# coringaM0.net
KiCad netlist of a schematic drawn in EAGLE
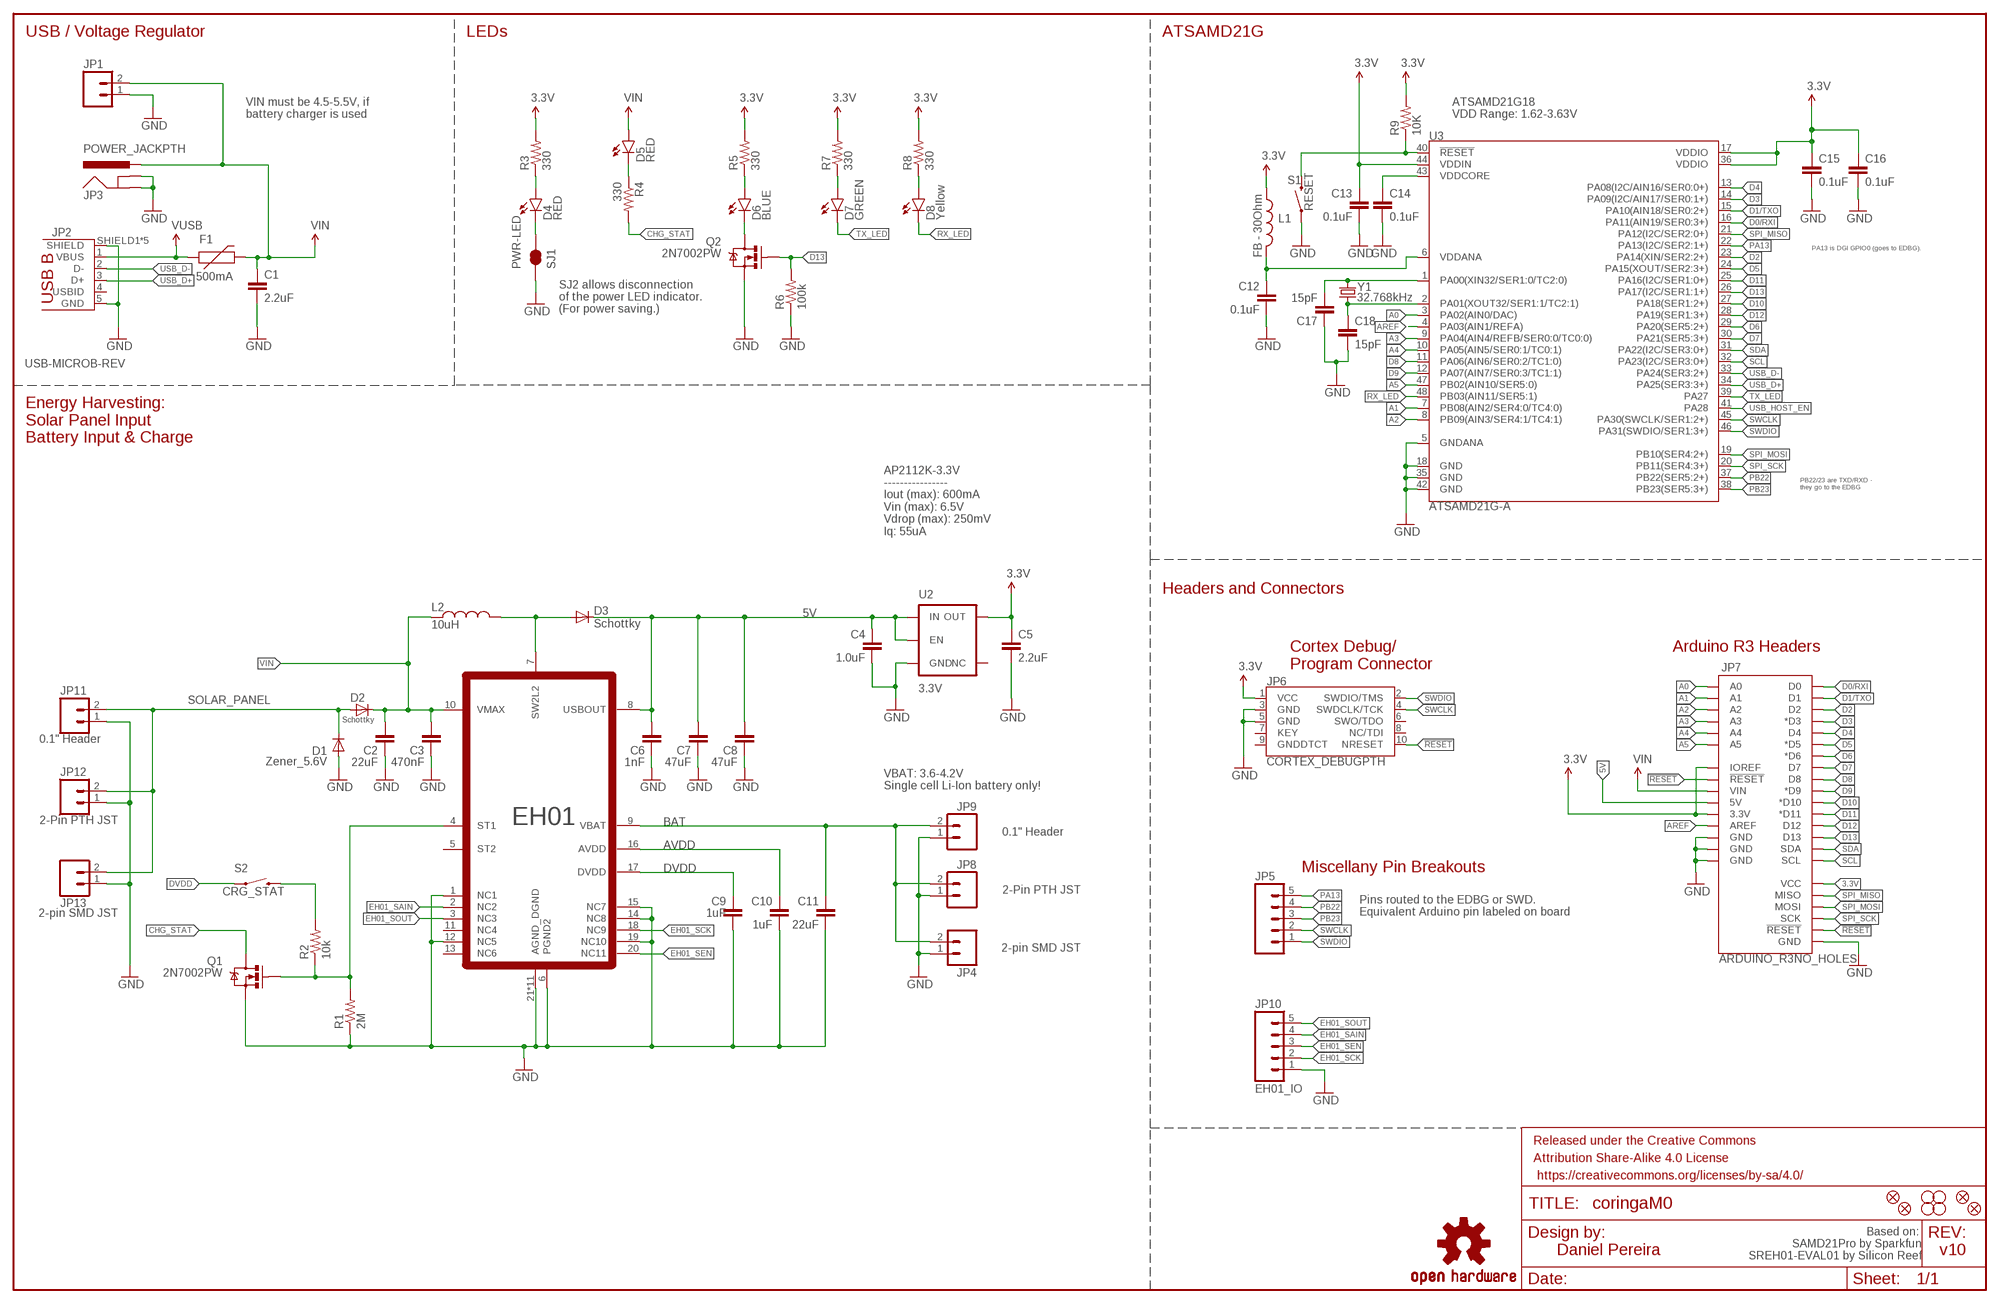
[diagram p0: schematic, sheet 1]

(export (version "E")
  (design (tool "Eeschema 10.0.6"))
  (components
    (comp (ref "C1")
      (value "2.2uF")
      (footprint "eagle-import:1206")
      (libsource (lib "eagle-import") (part "CAP1206"))
    )
    (comp (ref "C2")
      (value "22uF")
      (footprint "eagle-import:RCL_C0805")
      (libsource (lib "eagle-import") (part "CAPC0805"))
    )
    (comp (ref "C3")
      (value "470nF")
      (footprint "eagle-import:RCL_C1206")
      (libsource (lib "eagle-import") (part "CAPC1206"))
    )
    (comp (ref "C4")
      (value "1.0uF")
      (footprint "eagle-import:0805-CAP")
      (libsource (lib "eagle-import") (part "1.0UF-25V-+80/-20(0805){dblquote}"))
    )
    (comp (ref "C5")
      (value "2.2uF")
      (footprint "eagle-import:1206")
      (libsource (lib "eagle-import") (part "CAP1206"))
    )
    (comp (ref "C6")
      (value "1nF")
      (footprint "eagle-import:RCL_C1206K")
      (libsource (lib "eagle-import") (part "CAPC1206K"))
    )
    (comp (ref "C7")
      (value "47uF")
      (footprint "eagle-import:RCL_C1206K")
      (libsource (lib "eagle-import") (part "CAPC1206K"))
    )
    (comp (ref "C8")
      (value "47uF")
      (footprint "eagle-import:RCL_C1206K")
      (libsource (lib "eagle-import") (part "CAPC1206K"))
    )
    (comp (ref "C9")
      (value "1uF")
      (footprint "eagle-import:RCL_C0402")
      (libsource (lib "eagle-import") (part "CAPC0402"))
    )
    (comp (ref "C10")
      (value "1uF")
      (footprint "eagle-import:RCL_C0402")
      (libsource (lib "eagle-import") (part "CAPC0402"))
    )
    (comp (ref "C11")
      (value "22uF")
      (footprint "eagle-import:RCL_C0805")
      (libsource (lib "eagle-import") (part "CAPC0805"))
    )
    (comp (ref "C12")
      (value "0.1uF")
      (footprint "eagle-import:0603-CAP")
      (libsource (lib "eagle-import") (part "0.1UF-25V(+80/-20%)(0603)"))
    )
    (comp (ref "C13")
      (value "0.1uF")
      (footprint "eagle-import:0603-CAP")
      (libsource (lib "eagle-import") (part "0.1UF-25V(+80/-20%)(0603)"))
    )
    (comp (ref "C14")
      (value "0.1uF")
      (footprint "eagle-import:0603-CAP")
      (libsource (lib "eagle-import") (part "0.1UF-25V(+80/-20%)(0603)"))
    )
    (comp (ref "C15")
      (value "0.1uF")
      (footprint "eagle-import:0603-CAP")
      (libsource (lib "eagle-import") (part "0.1UF-25V(+80/-20%)(0603)"))
    )
    (comp (ref "C16")
      (value "0.1uF")
      (footprint "eagle-import:0603-CAP")
      (libsource (lib "eagle-import") (part "0.1UF-25V(+80/-20%)(0603)"))
    )
    (comp (ref "C17")
      (value "15pF")
      (footprint "eagle-import:0603-CAP")
      (libsource (lib "eagle-import") (part "15PF-50V-5%(0603)"))
    )
    (comp (ref "C18")
      (value "15pF")
      (footprint "eagle-import:0603-CAP")
      (libsource (lib "eagle-import") (part "15PF-50V-5%(0603)"))
    )
    (comp (ref "D1")
      (value "Zener_5.6V")
      (footprint "eagle-import:DO-214AC")
      (libsource (lib "eagle-import") (part "DIODE-DO-214AC"))
    )
    (comp (ref "D2")
      (value "Schottky")
      (footprint "eagle-import:DO-214AC")
      (libsource (lib "eagle-import") (part "DIODE-DO-214AC"))
    )
    (comp (ref "D3")
      (value "Schottky")
      (footprint "eagle-import:DO-214AC")
      (libsource (lib "eagle-import") (part "DIODE-DO-214AC"))
    )
    (comp (ref "D4")
      (value "RED")
      (footprint "eagle-import:LED-0603")
      (libsource (lib "eagle-import") (part "LED-RED0603"))
    )
    (comp (ref "D5")
      (value "RED")
      (footprint "eagle-import:LED-0603")
      (libsource (lib "eagle-import") (part "LED-RED0603"))
    )
    (comp (ref "D6")
      (value "BLUE")
      (footprint "eagle-import:LED-0603")
      (libsource (lib "eagle-import") (part "LED-BLUE0603"))
    )
    (comp (ref "D7")
      (value "GREEN")
      (footprint "eagle-import:LED-0603")
      (libsource (lib "eagle-import") (part "LED-GREEN0603"))
    )
    (comp (ref "D8")
      (value "Yellow")
      (footprint "eagle-import:LED-0603")
      (libsource (lib "eagle-import") (part "LED-YELLOW0603"))
    )
    (comp (ref "F1")
      (value "500mA")
      (footprint "eagle-import:PTC-1206")
      (libsource (lib "eagle-import") (part "PTCSMD"))
    )
    (comp (ref "FD1")
      (value "FIDUCIAL-VIA")
      (footprint "eagle-import:FIDUCIAL-VIA")
      (libsource (lib "eagle-import") (part "FIDUCIAL-VIA"))
    )
    (comp (ref "FD2")
      (value "FIDUCIAL-VIA")
      (footprint "eagle-import:FIDUCIAL-VIA")
      (libsource (lib "eagle-import") (part "FIDUCIAL-VIA"))
    )
    (comp (ref "FID1")
      (value "FIDUCIAL1X2")
      (footprint "eagle-import:FIDUCIAL-1X2")
      (libsource (lib "eagle-import") (part "FIDUCIAL1X2"))
    )
    (comp (ref "FID2")
      (value "FIDUCIAL1X2")
      (footprint "eagle-import:FIDUCIAL-1X2")
      (libsource (lib "eagle-import") (part "FIDUCIAL1X2"))
    )
    (comp (ref "FRAME1")
      (value "FRAME-LEDGER")
      (footprint "eagle-import:CREATIVE_COMMONS")
      (libsource (lib "eagle-import") (part "FRAME-LEDGER"))
    )
    (comp (ref "JP1")
      (value "M02PTH")
      (footprint "eagle-import:1X02")
      (libsource (lib "eagle-import") (part "M02PTH"))
    )
    (comp (ref "JP2")
      (value "USB-MICROB-REV")
      (footprint "eagle-import:USB-B-MICRO-REV-SMD")
      (fields (field (name "MPN") "ZX62R-B-5P"))
      (libsource (lib "eagle-import") (part "USB-MICROB-REV"))
    )
    (comp (ref "JP3")
      (value "POWER_JACKPTH")
      (footprint "eagle-import:POWER_JACK_PTH")
      (libsource (lib "eagle-import") (part "POWER_JACKPTH"))
    )
    (comp (ref "JP4")
      (value "M02-JST-2MM-SMT")
      (footprint "eagle-import:JST-2-SMD")
      (libsource (lib "eagle-import") (part "M02-JST-2MM-SMT"))
    )
    (comp (ref "JP5")
      (value "M05NO_SILK")
      (footprint "eagle-import:1X05_NO_SILK")
      (libsource (lib "eagle-import") (part "M05NO_SILK"))
    )
    (comp (ref "JP6")
      (value "CORTEX_DEBUGPTH")
      (footprint "eagle-import:2X5-PTH-1.27MM")
      (libsource (lib "eagle-import") (part "CORTEX_DEBUGPTH"))
    )
    (comp (ref "JP7")
      (value "ARDUINO_R3NO_HOLES")
      (footprint "eagle-import:ARDUINO_R3_NO_HOLES")
      (libsource (lib "eagle-import") (part "ARDUINO_R3NO_HOLES"))
    )
    (comp (ref "JP8")
      (value "M02-JST-2-PTH-NO_SILK")
      (footprint "eagle-import:JST-2-PTH-NS")
      (libsource (lib "eagle-import") (part "M02-JST-2-PTH-NO_SILK"))
    )
    (comp (ref "JP9")
      (value "M021X02_NO_SILK")
      (footprint "eagle-import:1X02_NO_SILK")
      (libsource (lib "eagle-import") (part "M021X02_NO_SILK"))
    )
    (comp (ref "JP10")
      (value "EH01_IO")
      (footprint "eagle-import:1X05_NO_SILK")
      (libsource (lib "eagle-import") (part "M05NO_SILK"))
    )
    (comp (ref "JP11")
      (value "M021X02_NO_SILK")
      (footprint "eagle-import:1X02_NO_SILK")
      (libsource (lib "eagle-import") (part "M021X02_NO_SILK"))
    )
    (comp (ref "JP12")
      (value "M02-JST-2-PTH-NO_SILK")
      (footprint "eagle-import:JST-2-PTH-NS")
      (libsource (lib "eagle-import") (part "M02-JST-2-PTH-NO_SILK"))
    )
    (comp (ref "JP13")
      (value "M02-JST-2MM-SMT")
      (footprint "eagle-import:JST-2-SMD")
      (libsource (lib "eagle-import") (part "M02-JST-2MM-SMT"))
    )
    (comp (ref "L1")
      (value "FB - 30Ohm")
      (footprint "eagle-import:0603")
      (libsource (lib "eagle-import") (part "INDUCTOR0603"))
    )
    (comp (ref "L2")
      (value "10uH")
      (footprint "eagle-import:SRN4065-100M")
      (libsource (lib "eagle-import") (part "INDUCTOR-SRN4065"))
    )
    (comp (ref "LOGO3")
      (value "OSHW-LOGOS")
      (footprint "eagle-import:OSHW-LOGO-S")
      (libsource (lib "eagle-import") (part "OSHW-LOGOS"))
    )
    (comp (ref "LOGO4")
      (value "OSHW-LOGOL")
      (footprint "eagle-import:OSHW-LOGO-L")
      (libsource (lib "eagle-import") (part "OSHW-LOGOL"))
    )
    (comp (ref "Q1")
      (value "2N7002PW")
      (footprint "eagle-import:SOT323")
      (libsource (lib "eagle-import") (part "MOSFET-NCHANNEL2N7002PW"))
    )
    (comp (ref "Q2")
      (value "2N7002PW")
      (footprint "eagle-import:SOT323")
      (libsource (lib "eagle-import") (part "MOSFET-NCHANNEL2N7002PW"))
    )
    (comp (ref "R1")
      (value "2M")
      (footprint "eagle-import:RESISTOR_R0402")
      (libsource (lib "eagle-import") (part "RESR0402"))
    )
    (comp (ref "R2")
      (value "10k")
      (footprint "eagle-import:RESISTOR_R0402")
      (libsource (lib "eagle-import") (part "RESR0402"))
    )
    (comp (ref "R3")
      (value "330")
      (footprint "eagle-import:0603-RES")
      (libsource (lib "eagle-import") (part "330OHM1/10W1%(0603)"))
    )
    (comp (ref "R4")
      (value "330")
      (footprint "eagle-import:0603-RES")
      (libsource (lib "eagle-import") (part "330OHM1/10W1%(0603)"))
    )
    (comp (ref "R5")
      (value "330")
      (footprint "eagle-import:0603-RES")
      (libsource (lib "eagle-import") (part "330OHM1/10W1%(0603)"))
    )
    (comp (ref "R6")
      (value "100k")
      (footprint "eagle-import:0603-RES")
      (libsource (lib "eagle-import") (part "100KOHM-1/10W-1%(0603)"))
    )
    (comp (ref "R7")
      (value "330")
      (footprint "eagle-import:0603-RES")
      (libsource (lib "eagle-import") (part "330OHM1/10W1%(0603)"))
    )
    (comp (ref "R8")
      (value "330")
      (footprint "eagle-import:0603-RES")
      (libsource (lib "eagle-import") (part "330OHM1/10W1%(0603)"))
    )
    (comp (ref "R9")
      (value "10K")
      (footprint "eagle-import:0603-RES")
      (libsource (lib "eagle-import") (part "10KOHM-1/10W-1%(0603)0603"))
    )
    (comp (ref "S1")
      (value "RESET")
      (footprint "eagle-import:TACTILE-SWITCH-SMD")
      (libsource (lib "eagle-import") (part "SWITCH-MOMENTARY-2SMD"))
    )
    (comp (ref "S2")
      (value "CRG_STAT")
      (footprint "eagle-import:TACTILE-SWITCH-SMD")
      (libsource (lib "eagle-import") (part "SWITCH-MOMENTARY-2SMD"))
    )
    (comp (ref "SJ1")
      (value "PWR-LED")
      (footprint "eagle-import:PAD-JUMPER-2-NC_BY_TRACE_NO_SILK")
      (libsource (lib "eagle-import") (part "JUMPER-PAD-2-NC_BY_TRACENO_SILK"))
    )
    (comp (ref "STANDOFF1")
      (value "STAND-OFF")
      (footprint "eagle-import:STAND-OFF")
      (libsource (lib "eagle-import") (part "STAND-OFF"))
    )
    (comp (ref "STANDOFF2")
      (value "STAND-OFF")
      (footprint "eagle-import:STAND-OFF")
      (libsource (lib "eagle-import") (part "STAND-OFF"))
    )
    (comp (ref "STANDOFF3")
      (value "STAND-OFF")
      (footprint "eagle-import:STAND-OFF")
      (libsource (lib "eagle-import") (part "STAND-OFF"))
    )
    (comp (ref "STANDOFF4")
      (value "STAND-OFF")
      (footprint "eagle-import:STAND-OFF")
      (libsource (lib "eagle-import") (part "STAND-OFF"))
    )
    (comp (ref "U1")
      (value "EH01")
      (footprint "eagle-import:QFN20")
      (libsource (lib "eagle-import") (part "EH01-P02"))
    )
    (comp (ref "U2")
      (value "3.3V")
      (footprint "eagle-import:SOT23-5")
      (libsource (lib "eagle-import") (part "V_REG_AP2112K-3.3V"))
    )
    (comp (ref "U3")
      (value "ATSAMD21G-A")
      (footprint "eagle-import:TQFP-48")
      (libsource (lib "eagle-import") (part "ATSAMD21G-A"))
    )
    (comp (ref "Y1")
      (value "32.768kHz")
      (footprint "eagle-import:CRYSTAL-SMD-3.2X1.5MM")
      (libsource (lib "eagle-import") (part "CRYSTAL3.2X1.5MM"))
    )
  )
  (nets
    (net (code "1") (name "/AVDD") (class "Default")
      (node (ref "C10") (pin "2") (pinfunction "2_2") (pintype "passive"))
      (node (ref "U1") (pin "16") (pinfunction "AVDD_16") (pintype "bidirectional"))
    )
    (net (code "2") (name "/BAT") (class "Default")
      (node (ref "C11") (pin "2") (pinfunction "2_2") (pintype "passive"))
      (node (ref "JP4") (pin "2") (pinfunction "1_2") (pintype "passive"))
      (node (ref "JP8") (pin "2") (pinfunction "2_2") (pintype "passive"))
      (node (ref "JP9") (pin "2") (pinfunction "2_2") (pintype "passive"))
      (node (ref "U1") (pin "9") (pinfunction "VBAT_9") (pintype "bidirectional"))
    )
    (net (code "3") (name "/SOLAR_PANEL") (class "Default")
      (node (ref "D1") (pin "C") (pinfunction "C_C") (pintype "passive"))
      (node (ref "D2") (pin "A") (pinfunction "A_A") (pintype "passive"))
      (node (ref "JP11") (pin "2") (pinfunction "2_2") (pintype "passive"))
      (node (ref "JP12") (pin "2") (pinfunction "2_2") (pintype "passive"))
      (node (ref "JP13") (pin "2") (pinfunction "1_2") (pintype "passive"))
    )
    (net (code "4") (name "/~{RESET}") (class "Default")
      (node (ref "JP6") (pin "10") (pinfunction "NRESET_10") (pintype "bidirectional"))
      (node (ref "JP7") (pin "RESET@1") (pinfunction "~{RESET}_RESET@1") (pintype "bidirectional"))
      (node (ref "JP7") (pin "RESET@2") (pinfunction "~{RESET}_RESET@2") (pintype "bidirectional"))
      (node (ref "R9") (pin "1") (pinfunction "1_1") (pintype "passive"))
      (node (ref "S1") (pin "3") (pinfunction "2_3") (pintype "passive"))
      (node (ref "U3") (pin "40") (pinfunction "~{RESET}_40") (pintype "bidirectional"))
    )
    (net (code "5") (name "3.3V") (class "Default")
      (node (ref "C13") (pin "1") (pinfunction "1_1") (pintype "passive"))
      (node (ref "C15") (pin "1") (pinfunction "1_1") (pintype "passive"))
      (node (ref "C16") (pin "1") (pinfunction "1_1") (pintype "passive"))
      (node (ref "C5") (pin "1") (pinfunction "1_1") (pintype "passive"))
      (node (ref "JP6") (pin "1") (pinfunction "VCC_1") (pintype "bidirectional"))
      (node (ref "JP7") (pin "3.3V") (pinfunction "3.3V_3.3V") (pintype "bidirectional"))
      (node (ref "JP7") (pin "IOREF") (pinfunction "IOREF_IOREF") (pintype "bidirectional"))
      (node (ref "JP7") (pin "VCC") (pinfunction "VCC_VCC") (pintype "bidirectional"))
      (node (ref "L1") (pin "1") (pinfunction "1_1") (pintype "passive"))
      (node (ref "R3") (pin "2") (pinfunction "2_2") (pintype "passive"))
      (node (ref "R5") (pin "2") (pinfunction "2_2") (pintype "passive"))
      (node (ref "R7") (pin "2") (pinfunction "2_2") (pintype "passive"))
      (node (ref "R8") (pin "2") (pinfunction "2_2") (pintype "passive"))
      (node (ref "R9") (pin "2") (pinfunction "2_2") (pintype "passive"))
      (node (ref "U2") (pin "5") (pinfunction "OUT_5") (pintype "passive"))
      (node (ref "U3") (pin "17") (pinfunction "VDDIO_17") (pintype "bidirectional"))
      (node (ref "U3") (pin "36") (pinfunction "VDDIO_36") (pintype "bidirectional"))
      (node (ref "U3") (pin "44") (pinfunction "VDDIN_44") (pintype "bidirectional"))
    )
    (net (code "6") (name "5V") (class "Default")
      (node (ref "C4") (pin "1") (pinfunction "1_1") (pintype "passive"))
      (node (ref "C6") (pin "2") (pinfunction "2_2") (pintype "passive"))
      (node (ref "C7") (pin "2") (pinfunction "2_2") (pintype "passive"))
      (node (ref "C8") (pin "2") (pinfunction "2_2") (pintype "passive"))
      (node (ref "D3") (pin "C") (pinfunction "C_C") (pintype "passive"))
      (node (ref "JP7") (pin "5V") (pinfunction "5V_5V") (pintype "bidirectional"))
      (node (ref "U1") (pin "8") (pinfunction "USBOUT_8") (pintype "bidirectional"))
      (node (ref "U2") (pin "1") (pinfunction "IN_1") (pintype "input"))
      (node (ref "U2") (pin "3") (pinfunction "EN_3") (pintype "input"))
    )
    (net (code "7") (name "A0") (class "Default")
      (node (ref "JP7") (pin "A0") (pinfunction "A0_A0") (pintype "bidirectional"))
      (node (ref "U3") (pin "3") (pinfunction "PA02(AIN0/DAC)_3") (pintype "bidirectional"))
    )
    (net (code "8") (name "A1") (class "Default")
      (node (ref "JP7") (pin "A1") (pinfunction "A1_A1") (pintype "bidirectional"))
      (node (ref "U3") (pin "7") (pinfunction "PB08(AIN2/SER4:0/TC4:0)_7") (pintype "bidirectional"))
    )
    (net (code "9") (name "A2") (class "Default")
      (node (ref "JP7") (pin "A2") (pinfunction "A2_A2") (pintype "bidirectional"))
      (node (ref "U3") (pin "8") (pinfunction "PB09(AIN3/SER4:1/TC4:1)_8") (pintype "bidirectional"))
    )
    (net (code "10") (name "A3") (class "Default")
      (node (ref "JP7") (pin "A3") (pinfunction "A3_A3") (pintype "bidirectional"))
      (node (ref "U3") (pin "9") (pinfunction "PA04(AIN4/REFB/SER0:0/TC0:0)_9") (pintype "bidirectional"))
    )
    (net (code "11") (name "A4") (class "Default")
      (node (ref "JP7") (pin "A4") (pinfunction "A4_A4") (pintype "bidirectional"))
      (node (ref "U3") (pin "10") (pinfunction "PA05(AIN5/SER0:1/TC0:1)_10") (pintype "bidirectional"))
    )
    (net (code "12") (name "A5") (class "Default")
      (node (ref "JP7") (pin "A5") (pinfunction "A5_A5") (pintype "bidirectional"))
      (node (ref "U3") (pin "47") (pinfunction "PB02(AIN10/SER5:0)_47") (pintype "bidirectional"))
    )
    (net (code "13") (name "AREF") (class "Default")
      (node (ref "JP7") (pin "AREF") (pinfunction "AREF_AREF") (pintype "bidirectional"))
      (node (ref "U3") (pin "4") (pinfunction "PA03(AIN1/REFA)_4") (pintype "bidirectional"))
    )
    (net (code "14") (name "CHG_STAT") (class "Default")
      (node (ref "Q1") (pin "3") (pinfunction "D_3") (pintype "passive"))
      (node (ref "R4") (pin "2") (pinfunction "2_2") (pintype "passive"))
    )
    (net (code "15") (name "D0{slash}RXI") (class "Default")
      (node (ref "JP7") (pin "D0") (pinfunction "D0_D0") (pintype "bidirectional"))
      (node (ref "U3") (pin "16") (pinfunction "PA11(AIN19/SER0:3+)_16") (pintype "bidirectional"))
    )
    (net (code "16") (name "D1{slash}TXO") (class "Default")
      (node (ref "JP7") (pin "D1") (pinfunction "D1_D1") (pintype "bidirectional"))
      (node (ref "U3") (pin "15") (pinfunction "PA10(AIN18/SER0:2+)_15") (pintype "bidirectional"))
    )
    (net (code "17") (name "D2") (class "Default")
      (node (ref "JP7") (pin "D2") (pinfunction "D2_D2") (pintype "bidirectional"))
      (node (ref "U3") (pin "23") (pinfunction "PA14(XIN/SER2:2+)_23") (pintype "bidirectional"))
    )
    (net (code "18") (name "D3") (class "Default")
      (node (ref "JP7") (pin "D3") (pinfunction "*D3_D3") (pintype "bidirectional"))
      (node (ref "U3") (pin "14") (pinfunction "PA09(I2C/AIN17/SER0:1+)_14") (pintype "bidirectional"))
    )
    (net (code "19") (name "D4") (class "Default")
      (node (ref "JP7") (pin "D4") (pinfunction "D4_D4") (pintype "bidirectional"))
      (node (ref "U3") (pin "13") (pinfunction "PA08(I2C/AIN16/SER0:0+)_13") (pintype "bidirectional"))
    )
    (net (code "20") (name "D5") (class "Default")
      (node (ref "JP7") (pin "D5") (pinfunction "*D5_D5") (pintype "bidirectional"))
      (node (ref "U3") (pin "24") (pinfunction "PA15(XOUT/SER2:3+)_24") (pintype "bidirectional"))
    )
    (net (code "21") (name "D6") (class "Default")
      (node (ref "JP7") (pin "D6") (pinfunction "*D6_D6") (pintype "bidirectional"))
      (node (ref "U3") (pin "29") (pinfunction "PA20(SER5:2+)_29") (pintype "bidirectional"))
    )
    (net (code "22") (name "D7") (class "Default")
      (node (ref "JP7") (pin "D7") (pinfunction "D7_D7") (pintype "bidirectional"))
      (node (ref "U3") (pin "30") (pinfunction "PA21(SER5:3+)_30") (pintype "bidirectional"))
    )
    (net (code "23") (name "D8") (class "Default")
      (node (ref "JP7") (pin "D8") (pinfunction "D8_D8") (pintype "bidirectional"))
      (node (ref "U3") (pin "11") (pinfunction "PA06(AIN6/SER0:2/TC1:0)_11") (pintype "bidirectional"))
    )
    (net (code "24") (name "D9") (class "Default")
      (node (ref "JP7") (pin "D9") (pinfunction "*D9_D9") (pintype "bidirectional"))
      (node (ref "U3") (pin "12") (pinfunction "PA07(AIN7/SER0:3/TC1:1)_12") (pintype "bidirectional"))
    )
    (net (code "25") (name "D10") (class "Default")
      (node (ref "JP7") (pin "D10") (pinfunction "*D10_D10") (pintype "bidirectional"))
      (node (ref "U3") (pin "27") (pinfunction "PA18(SER1:2+)_27") (pintype "bidirectional"))
    )
    (net (code "26") (name "D11") (class "Default")
      (node (ref "JP7") (pin "D11") (pinfunction "*D11_D11") (pintype "bidirectional"))
      (node (ref "U3") (pin "25") (pinfunction "PA16(I2C/SER1:0+)_25") (pintype "bidirectional"))
    )
    (net (code "27") (name "D12") (class "Default")
      (node (ref "JP7") (pin "D12") (pinfunction "D12_D12") (pintype "bidirectional"))
      (node (ref "U3") (pin "28") (pinfunction "PA19(SER1:3+)_28") (pintype "bidirectional"))
    )
    (net (code "28") (name "D13") (class "Default")
      (node (ref "JP7") (pin "D13") (pinfunction "D13_D13") (pintype "bidirectional"))
      (node (ref "Q2") (pin "1") (pinfunction "G_1") (pintype "passive"))
      (node (ref "R6") (pin "2") (pinfunction "2_2") (pintype "passive"))
      (node (ref "U3") (pin "26") (pinfunction "PA17(I2C/SER1:1+)_26") (pintype "bidirectional"))
    )
    (net (code "29") (name "DVDD") (class "Default")
      (node (ref "C9") (pin "2") (pinfunction "2_2") (pintype "passive"))
      (node (ref "S2") (pin "1") (pinfunction "1_1") (pintype "passive"))
      (node (ref "U1") (pin "17") (pinfunction "DVDD_17") (pintype "bidirectional"))
    )
    (net (code "30") (name "EH01_SAIN") (class "Default")
      (node (ref "JP10") (pin "4") (pinfunction "4_4") (pintype "passive"))
      (node (ref "U1") (pin "2") (pinfunction "NC2_2") (pintype "bidirectional"))
    )
    (net (code "31") (name "EH01_SCK") (class "Default")
      (node (ref "JP10") (pin "2") (pinfunction "2_2") (pintype "passive"))
      (node (ref "U1") (pin "18") (pinfunction "NC9_18") (pintype "bidirectional"))
    )
    (net (code "32") (name "EH01_SEN") (class "Default")
      (node (ref "JP10") (pin "3") (pinfunction "3_3") (pintype "passive"))
      (node (ref "U1") (pin "20") (pinfunction "NC11_20") (pintype "bidirectional"))
    )
    (net (code "33") (name "EH01_SOUT") (class "Default")
      (node (ref "JP10") (pin "5") (pinfunction "5_5") (pintype "passive"))
      (node (ref "U1") (pin "3") (pinfunction "NC3_3") (pintype "bidirectional"))
    )
    (net (code "34") (name "GND") (class "Default")
      (node (ref "C1") (pin "2") (pinfunction "2_2") (pintype "passive"))
      (node (ref "C10") (pin "1") (pinfunction "1_1") (pintype "passive"))
      (node (ref "C11") (pin "1") (pinfunction "1_1") (pintype "passive"))
      (node (ref "C12") (pin "2") (pinfunction "2_2") (pintype "passive"))
      (node (ref "C13") (pin "2") (pinfunction "2_2") (pintype "passive"))
      (node (ref "C14") (pin "2") (pinfunction "2_2") (pintype "passive"))
      (node (ref "C15") (pin "2") (pinfunction "2_2") (pintype "passive"))
      (node (ref "C16") (pin "2") (pinfunction "2_2") (pintype "passive"))
      (node (ref "C17") (pin "1") (pinfunction "1_1") (pintype "passive"))
      (node (ref "C18") (pin "2") (pinfunction "2_2") (pintype "passive"))
      (node (ref "C2") (pin "1") (pinfunction "1_1") (pintype "passive"))
      (node (ref "C3") (pin "1") (pinfunction "1_1") (pintype "passive"))
      (node (ref "C4") (pin "2") (pinfunction "2_2") (pintype "passive"))
      (node (ref "C5") (pin "2") (pinfunction "2_2") (pintype "passive"))
      (node (ref "C6") (pin "1") (pinfunction "1_1") (pintype "passive"))
      (node (ref "C7") (pin "1") (pinfunction "1_1") (pintype "passive"))
      (node (ref "C8") (pin "1") (pinfunction "1_1") (pintype "passive"))
      (node (ref "C9") (pin "1") (pinfunction "1_1") (pintype "passive"))
      (node (ref "D1") (pin "A") (pinfunction "A_A") (pintype "passive"))
      (node (ref "JP1") (pin "1") (pinfunction "1_1") (pintype "passive"))
      (node (ref "JP10") (pin "1") (pinfunction "1_1") (pintype "passive"))
      (node (ref "JP11") (pin "1") (pinfunction "1_1") (pintype "passive"))
      (node (ref "JP12") (pin "1") (pinfunction "1_1") (pintype "passive"))
      (node (ref "JP13") (pin "1") (pinfunction "2_1") (pintype "passive"))
      (node (ref "JP2") (pin "5") (pinfunction "GND_5") (pintype "bidirectional"))
      (node (ref "JP2") (pin "SHIELD1") (pinfunction "SHIELD_SHIELD1") (pintype "bidirectional"))
      (node (ref "JP2") (pin "SHIELD2") (pinfunction "SHIELD_SHIELD2") (pintype "bidirectional"))
      (node (ref "JP2") (pin "SHIELD3") (pinfunction "SHIELD_SHIELD3") (pintype "bidirectional"))
      (node (ref "JP2") (pin "SHIELD4") (pinfunction "SHIELD_SHIELD4") (pintype "bidirectional"))
      (node (ref "JP2") (pin "SHIELD5") (pinfunction "SHIELD_SHIELD5") (pintype "bidirectional"))
      (node (ref "JP3") (pin "GND") (pinfunction "GND_GND") (pintype "bidirectional"))
      (node (ref "JP3") (pin "GNDBREAK") (pinfunction "GNDBREAK_GNDBREAK") (pintype "bidirectional"))
      (node (ref "JP4") (pin "1") (pinfunction "2_1") (pintype "passive"))
      (node (ref "JP6") (pin "3") (pinfunction "GND_3") (pintype "bidirectional"))
      (node (ref "JP6") (pin "5") (pinfunction "GND_5") (pintype "bidirectional"))
      (node (ref "JP7") (pin "GND@1") (pinfunction "GND_GND@1") (pintype "bidirectional"))
      (node (ref "JP7") (pin "GND@2") (pinfunction "GND_GND@2") (pintype "bidirectional"))
      (node (ref "JP7") (pin "GND@3") (pinfunction "GND_GND@3") (pintype "bidirectional"))
      (node (ref "JP7") (pin "GND@4") (pinfunction "GND_GND@4") (pintype "bidirectional"))
      (node (ref "JP8") (pin "1") (pinfunction "1_1") (pintype "passive"))
      (node (ref "JP9") (pin "1") (pinfunction "1_1") (pintype "passive"))
      (node (ref "Q1") (pin "2") (pinfunction "S_2") (pintype "passive"))
      (node (ref "Q2") (pin "2") (pinfunction "S_2") (pintype "passive"))
      (node (ref "R1") (pin "1") (pinfunction "1_1") (pintype "passive"))
      (node (ref "R6") (pin "1") (pinfunction "1_1") (pintype "passive"))
      (node (ref "S1") (pin "1") (pinfunction "1_1") (pintype "passive"))
      (node (ref "SJ1") (pin "1") (pinfunction "1_1") (pintype "passive"))
      (node (ref "U1") (pin "1") (pinfunction "NC1_1") (pintype "bidirectional"))
      (node (ref "U1") (pin "12") (pinfunction "NC5_12") (pintype "bidirectional"))
      (node (ref "U1") (pin "14") (pinfunction "NC8_14") (pintype "bidirectional"))
      (node (ref "U1") (pin "15") (pinfunction "NC7_15") (pintype "bidirectional"))
      (node (ref "U1") (pin "19") (pinfunction "NC10_19") (pintype "bidirectional"))
      (node (ref "U1") (pin "21") (pinfunction "AGND_DGND_21") (pintype "bidirectional"))
      (node (ref "U1") (pin "22") (pinfunction "AGND_DGND_22") (pintype "bidirectional"))
      (node (ref "U1") (pin "6") (pinfunction "PGND2_6") (pintype "bidirectional"))
      (node (ref "U1") (pin "P$1") (pinfunction "AGND_DGND_P$1") (pintype "bidirectional"))
      (node (ref "U1") (pin "P$2") (pinfunction "AGND_DGND_P$2") (pintype "bidirectional"))
      (node (ref "U1") (pin "P$3") (pinfunction "AGND_DGND_P$3") (pintype "bidirectional"))
      (node (ref "U1") (pin "P$4") (pinfunction "AGND_DGND_P$4") (pintype "bidirectional"))
      (node (ref "U1") (pin "P$5") (pinfunction "AGND_DGND_P$5") (pintype "bidirectional"))
      (node (ref "U1") (pin "P$6") (pinfunction "AGND_DGND_P$6") (pintype "bidirectional"))
      (node (ref "U1") (pin "P$7") (pinfunction "AGND_DGND_P$7") (pintype "bidirectional"))
      (node (ref "U1") (pin "P$8") (pinfunction "AGND_DGND_P$8") (pintype "bidirectional"))
      (node (ref "U1") (pin "P$9") (pinfunction "AGND_DGND_P$9") (pintype "bidirectional"))
      (node (ref "U2") (pin "2") (pinfunction "GND_2") (pintype "input"))
      (node (ref "U3") (pin "18") (pinfunction "GND_18") (pintype "bidirectional"))
      (node (ref "U3") (pin "35") (pinfunction "GND_35") (pintype "bidirectional"))
      (node (ref "U3") (pin "42") (pinfunction "GND_42") (pintype "bidirectional"))
      (node (ref "U3") (pin "5") (pinfunction "GNDANA_5") (pintype "bidirectional"))
    )
    (net (code "35") (name "Net-(D4-PadA)") (class "Default")
      (node (ref "D4") (pin "A") (pinfunction "A_A") (pintype "passive"))
      (node (ref "R3") (pin "1") (pinfunction "1_1") (pintype "passive"))
    )
    (net (code "36") (name "Net-(D4-PadC)") (class "Default")
      (node (ref "D4") (pin "C") (pinfunction "C_C") (pintype "passive"))
      (node (ref "SJ1") (pin "2") (pinfunction "2_2") (pintype "passive"))
    )
    (net (code "37") (name "Net-(D5-PadC)") (class "Default")
      (node (ref "D5") (pin "C") (pinfunction "C_C") (pintype "passive"))
      (node (ref "R4") (pin "1") (pinfunction "1_1") (pintype "passive"))
    )
    (net (code "38") (name "Net-(D6-PadA)") (class "Default")
      (node (ref "D6") (pin "A") (pinfunction "A_A") (pintype "passive"))
      (node (ref "R5") (pin "1") (pinfunction "1_1") (pintype "passive"))
    )
    (net (code "39") (name "Net-(D7-PadA)") (class "Default")
      (node (ref "D7") (pin "A") (pinfunction "A_A") (pintype "passive"))
      (node (ref "R7") (pin "1") (pinfunction "1_1") (pintype "passive"))
    )
    (net (code "40") (name "Net-(D8-PadA)") (class "Default")
      (node (ref "D8") (pin "A") (pinfunction "A_A") (pintype "passive"))
      (node (ref "R8") (pin "1") (pinfunction "1_1") (pintype "passive"))
    )
    (net (code "41") (name "Net-(L2-2)") (class "Default")
      (node (ref "D3") (pin "A") (pinfunction "A_A") (pintype "passive"))
      (node (ref "L2") (pin "P$2") (pinfunction "2_P$2") (pintype "bidirectional"))
      (node (ref "U1") (pin "7") (pinfunction "SW2L2_7") (pintype "bidirectional"))
    )
    (net (code "42") (name "Net-(Q1-G)") (class "Default")
      (node (ref "Q1") (pin "1") (pinfunction "G_1") (pintype "passive"))
      (node (ref "R1") (pin "2") (pinfunction "2_2") (pintype "passive"))
      (node (ref "R2") (pin "1") (pinfunction "1_1") (pintype "passive"))
      (node (ref "U1") (pin "4") (pinfunction "ST1_4") (pintype "bidirectional"))
    )
    (net (code "43") (name "Net-(Q2-D)") (class "Default")
      (node (ref "D6") (pin "C") (pinfunction "C_C") (pintype "passive"))
      (node (ref "Q2") (pin "3") (pinfunction "D_3") (pintype "passive"))
    )
    (net (code "44") (name "Net-(S2-2)") (class "Default")
      (node (ref "R2") (pin "2") (pinfunction "2_2") (pintype "passive"))
      (node (ref "S2") (pin "3") (pinfunction "2_3") (pintype "passive"))
    )
    (net (code "45") (name "Net-(U3-PA00(XIN32{slash}SER1:0{slash}TC2:0))") (class "Default")
      (node (ref "C17") (pin "2") (pinfunction "2_2") (pintype "passive"))
      (node (ref "U3") (pin "1") (pinfunction "PA00(XIN32/SER1:0/TC2:0)_1") (pintype "bidirectional"))
      (node (ref "Y1") (pin "P$2") (pinfunction "2_P$2") (pintype "passive"))
    )
    (net (code "46") (name "Net-(U3-PA01(XOUT32{slash}SER1:1{slash}TC2:1))") (class "Default")
      (node (ref "C18") (pin "1") (pinfunction "1_1") (pintype "passive"))
      (node (ref "U3") (pin "2") (pinfunction "PA01(XOUT32/SER1:1/TC2:1)_2") (pintype "bidirectional"))
      (node (ref "Y1") (pin "P$1") (pinfunction "1_P$1") (pintype "passive"))
    )
    (net (code "47") (name "Net-(U3-VDDANA)") (class "Default")
      (node (ref "C12") (pin "1") (pinfunction "1_1") (pintype "passive"))
      (node (ref "L1") (pin "2") (pinfunction "2_2") (pintype "passive"))
      (node (ref "U3") (pin "6") (pinfunction "VDDANA_6") (pintype "bidirectional"))
    )
    (net (code "48") (name "Net-(U3-VDDCORE)") (class "Default")
      (node (ref "C14") (pin "1") (pinfunction "1_1") (pintype "passive"))
      (node (ref "U3") (pin "43") (pinfunction "VDDCORE_43") (pintype "bidirectional"))
    )
    (net (code "49") (name "PA13") (class "Default")
      (node (ref "JP5") (pin "5") (pinfunction "5_5") (pintype "passive"))
      (node (ref "U3") (pin "22") (pinfunction "PA13(I2C/SER2:1+)_22") (pintype "bidirectional"))
    )
    (net (code "50") (name "PB22") (class "Default")
      (node (ref "JP5") (pin "4") (pinfunction "4_4") (pintype "passive"))
      (node (ref "U3") (pin "37") (pinfunction "PB22(SER5:2+)_37") (pintype "bidirectional"))
    )
    (net (code "51") (name "PB23") (class "Default")
      (node (ref "JP5") (pin "3") (pinfunction "3_3") (pintype "passive"))
      (node (ref "U3") (pin "38") (pinfunction "PB23(SER5:3+)_38") (pintype "bidirectional"))
    )
    (net (code "52") (name "RX_LED") (class "Default")
      (node (ref "D8") (pin "C") (pinfunction "C_C") (pintype "passive"))
      (node (ref "U3") (pin "48") (pinfunction "PB03(AIN11/SER5:1)_48") (pintype "bidirectional"))
    )
    (net (code "53") (name "SCL") (class "Default")
      (node (ref "JP7") (pin "SCL") (pinfunction "SCL_SCL") (pintype "bidirectional"))
      (node (ref "U3") (pin "32") (pinfunction "PA23(I2C/SER3:0+)_32") (pintype "bidirectional"))
    )
    (net (code "54") (name "SDA") (class "Default")
      (node (ref "JP7") (pin "SDA") (pinfunction "SDA_SDA") (pintype "bidirectional"))
      (node (ref "U3") (pin "31") (pinfunction "PA22(I2C/SER3:0+)_31") (pintype "bidirectional"))
    )
    (net (code "55") (name "SPI_MISO") (class "Default")
      (node (ref "JP7") (pin "MISO") (pinfunction "MISO_MISO") (pintype "bidirectional"))
      (node (ref "U3") (pin "21") (pinfunction "PA12(I2C/SER2:0+)_21") (pintype "bidirectional"))
    )
    (net (code "56") (name "SPI_MOSI") (class "Default")
      (node (ref "JP7") (pin "MOSI") (pinfunction "MOSI_MOSI") (pintype "bidirectional"))
      (node (ref "U3") (pin "19") (pinfunction "PB10(SER4:2+)_19") (pintype "bidirectional"))
    )
    (net (code "57") (name "SPI_SCK") (class "Default")
      (node (ref "JP7") (pin "SCK") (pinfunction "SCK_SCK") (pintype "bidirectional"))
      (node (ref "U3") (pin "20") (pinfunction "PB11(SER4:3+)_20") (pintype "bidirectional"))
    )
    (net (code "58") (name "SWCLK") (class "Default")
      (node (ref "JP5") (pin "2") (pinfunction "2_2") (pintype "passive"))
      (node (ref "JP6") (pin "4") (pinfunction "SWDCLK/TCK_4") (pintype "bidirectional"))
      (node (ref "U3") (pin "45") (pinfunction "PA30(SWCLK/SER1:2+)_45") (pintype "bidirectional"))
    )
    (net (code "59") (name "SWDIO") (class "Default")
      (node (ref "JP5") (pin "1") (pinfunction "1_1") (pintype "passive"))
      (node (ref "JP6") (pin "2") (pinfunction "SWDIO/TMS_2") (pintype "bidirectional"))
      (node (ref "U3") (pin "46") (pinfunction "PA31(SWDIO/SER1:3+)_46") (pintype "bidirectional"))
    )
    (net (code "60") (name "TX_LED") (class "Default")
      (node (ref "D7") (pin "C") (pinfunction "C_C") (pintype "passive"))
      (node (ref "U3") (pin "39") (pinfunction "PA27_39") (pintype "bidirectional"))
    )
    (net (code "61") (name "USB_D+") (class "Default")
      (node (ref "JP2") (pin "3") (pinfunction "D+_3") (pintype "bidirectional"))
      (node (ref "U3") (pin "34") (pinfunction "PA25(SER3:3+)_34") (pintype "bidirectional"))
    )
    (net (code "62") (name "USB_D-") (class "Default")
      (node (ref "JP2") (pin "2") (pinfunction "D-_2") (pintype "bidirectional"))
      (node (ref "U3") (pin "33") (pinfunction "PA24(SER3:2+)_33") (pintype "bidirectional"))
    )
    (net (code "63") (name "USB_HOST_EN") (class "Default")
      (node (ref "U3") (pin "41") (pinfunction "PA28_41") (pintype "bidirectional"))
    )
    (net (code "64") (name "VIN") (class "Default")
      (node (ref "C1") (pin "1") (pinfunction "1_1") (pintype "passive"))
      (node (ref "C2") (pin "2") (pinfunction "2_2") (pintype "passive"))
      (node (ref "C3") (pin "2") (pinfunction "2_2") (pintype "passive"))
      (node (ref "D2") (pin "C") (pinfunction "C_C") (pintype "passive"))
      (node (ref "D5") (pin "A") (pinfunction "A_A") (pintype "passive"))
      (node (ref "F1") (pin "2") (pinfunction "2_2") (pintype "bidirectional"))
      (node (ref "JP1") (pin "2") (pinfunction "2_2") (pintype "passive"))
      (node (ref "JP3") (pin "PWR") (pinfunction "PWR_PWR") (pintype "bidirectional"))
      (node (ref "JP7") (pin "VIN") (pinfunction "VIN_VIN") (pintype "bidirectional"))
      (node (ref "L2") (pin "P$1") (pinfunction "1_P$1") (pintype "bidirectional"))
      (node (ref "U1") (pin "10") (pinfunction "VMAX_10") (pintype "bidirectional"))
    )
    (net (code "65") (name "VUSB") (class "Default")
      (node (ref "F1") (pin "1") (pinfunction "1_1") (pintype "bidirectional"))
      (node (ref "JP2") (pin "1") (pinfunction "VBUS_1") (pintype "bidirectional"))
    )
    (net (code "66") (name "unconnected-(JP2-USBID-Pad4)") (class "Default")
      (node (ref "JP2") (pin "4") (pinfunction "USBID_4") (pintype "bidirectional"))
    )
    (net (code "67") (name "unconnected-(JP6-GNDDTCT-Pad9)") (class "Default")
      (node (ref "JP6") (pin "9") (pinfunction "GNDDTCT_9") (pintype "bidirectional"))
    )
    (net (code "68") (name "unconnected-(JP6-KEY-Pad7)") (class "Default")
      (node (ref "JP6") (pin "7") (pinfunction "KEY_7") (pintype "bidirectional"))
    )
    (net (code "69") (name "unconnected-(JP6-NC{slash}TDI-Pad8)") (class "Default")
      (node (ref "JP6") (pin "8") (pinfunction "NC/TDI_8") (pintype "bidirectional"))
    )
    (net (code "70") (name "unconnected-(JP6-SWO{slash}TDO-Pad6)") (class "Default")
      (node (ref "JP6") (pin "6") (pinfunction "SWO/TDO_6") (pintype "bidirectional"))
    )
    (net (code "71") (name "unconnected-(U1-NC4-Pad11)") (class "Default")
      (node (ref "U1") (pin "11") (pinfunction "NC4_11") (pintype "bidirectional"))
    )
    (net (code "72") (name "unconnected-(U1-NC6-Pad13)") (class "Default")
      (node (ref "U1") (pin "13") (pinfunction "NC6_13") (pintype "bidirectional"))
    )
    (net (code "73") (name "unconnected-(U1-ST2-Pad5)") (class "Default")
      (node (ref "U1") (pin "5") (pinfunction "ST2_5") (pintype "bidirectional"))
    )
    (net (code "74") (name "unconnected-(U2-NC-Pad4)") (class "Default")
      (node (ref "U2") (pin "4") (pinfunction "NC_4") (pintype "input"))
    )
  )
)
